# eurorack-passive-lpg.net
KiCad netlist of a schematic drawn in EAGLE
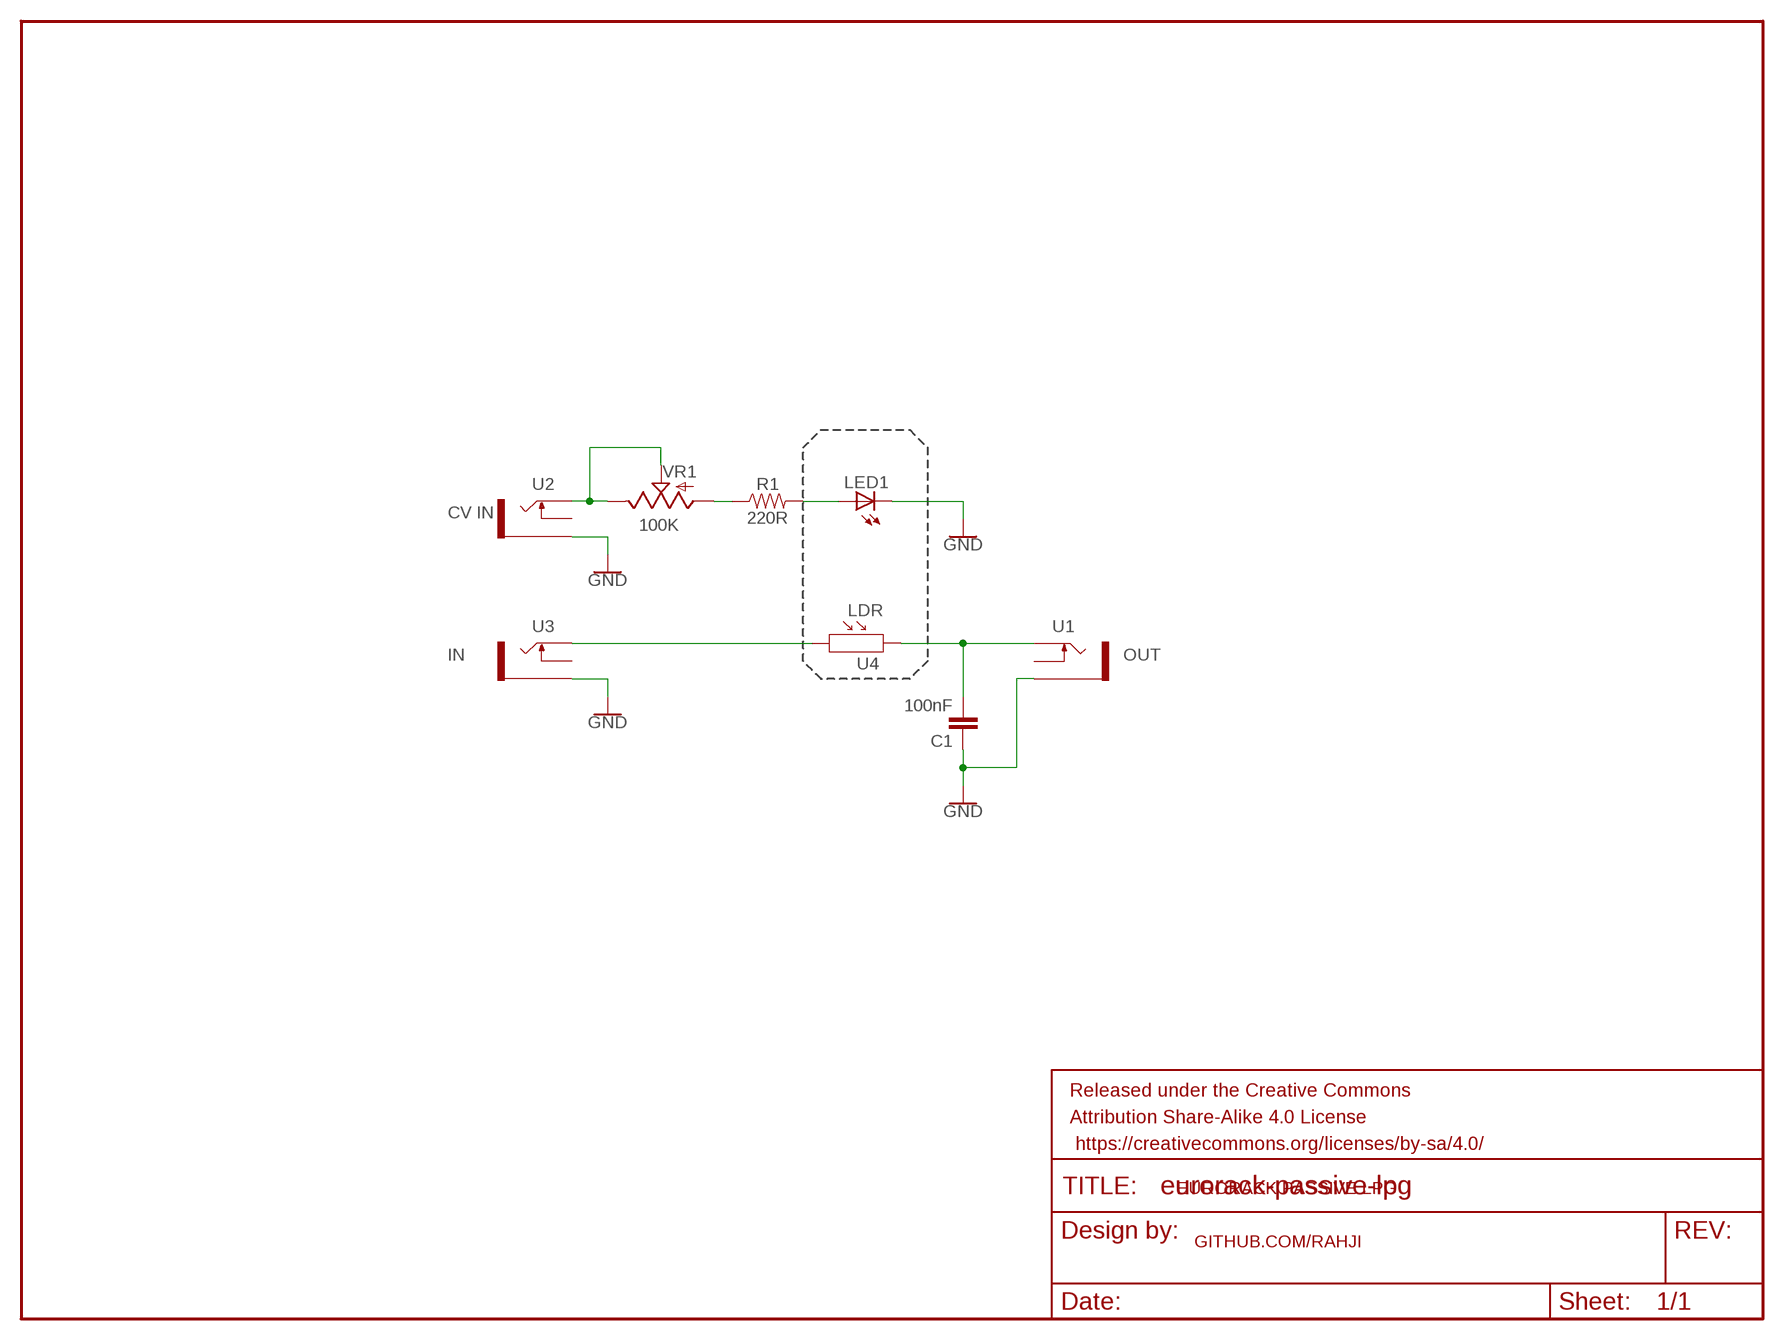
[diagram p0: schematic, sheet 1]

(export (version "E")
  (design (tool "Eeschema 10.0.6"))
  (components
    (comp (ref "C1")
      (value "100nF")
      (footprint "eagle-import:CAP-PTH-2.54")
      (libsource (lib "eagle-import") (part "22PF-PTH-2.54MM-200V-5%"))
    )
    (comp (ref "FRAME1")
      (value "FRAME-LETTERNO_PACKAGE")
      (footprint "eagle-import:DUMMY")
      (fields (field (name "DESIGNER") "Nobody"))
      (libsource (lib "eagle-import") (part "FRAME-LETTERNO_PACKAGE"))
    )
    (comp (ref "LED1")
      (value "LED5MM")
      (footprint "eagle-import:LED5MM")
      (libsource (lib "eagle-import") (part "LED5MM"))
    )
    (comp (ref "R1")
      (value "220R")
      (footprint "eagle-import:AXIAL-0.3")
      (libsource (lib "eagle-import") (part "100OHM-HORIZ-1/4W-1%"))
    )
    (comp (ref "U1")
      (value "OUT")
      (footprint "eagle-import:WQP-PJ301M-12_JACK")
      (libsource (lib "eagle-import") (part "THONKICONNNEW"))
    )
    (comp (ref "U2")
      (value "CV IN")
      (footprint "eagle-import:WQP-PJ301M-12_JACK")
      (libsource (lib "eagle-import") (part "THONKICONNNEW"))
    )
    (comp (ref "U3")
      (value "IN")
      (footprint "eagle-import:WQP-PJ301M-12_JACK")
      (libsource (lib "eagle-import") (part "THONKICONNNEW"))
    )
    (comp (ref "U4")
      (value "LDR")
      (footprint "eagle-import:SNR2-3.0")
      (fields (field (name "MPN") "PHOTORESISTOR-5528-10K"))
      (libsource (lib "eagle-import") (part "PHOTORESISTOR-5528-10K(2P-5.0X4.2MM)"))
    )
    (comp (ref "VR1")
      (value "100K")
      (footprint "eagle-import:9MM_SNAP-IN_POT")
      (libsource (lib "eagle-import") (part "9MM_SNAP-IN_POT_"))
    )
  )
  (nets
    (net (code "1") (name "GND") (class "Default")
      (node (ref "C1") (pin "1") (pinfunction "1_1") (pintype "passive"))
      (node (ref "LED1") (pin "K") (pinfunction "C_K") (pintype "passive"))
      (node (ref "U1") (pin "P$3_SLEEVE") (pinfunction "SLEEVE_P$3_SLEEVE") (pintype "passive"))
      (node (ref "U2") (pin "P$3_SLEEVE") (pinfunction "SLEEVE_P$3_SLEEVE") (pintype "passive"))
      (node (ref "U3") (pin "P$3_SLEEVE") (pinfunction "SLEEVE_P$3_SLEEVE") (pintype "passive"))
    )
    (net (code "2") (name "Net-(R1-1)") (class "Default")
      (node (ref "R1") (pin "P$1") (pinfunction "1_P$1") (pintype "passive"))
      (node (ref "VR1") (pin "1") (pinfunction "A_1") (pintype "passive"))
    )
    (net (code "3") (name "Net-(R1-2)") (class "Default")
      (node (ref "LED1") (pin "A") (pinfunction "A_A") (pintype "passive"))
      (node (ref "R1") (pin "P$2") (pinfunction "2_P$2") (pintype "passive"))
    )
    (net (code "4") (name "Net-(U1-TIP)") (class "Default")
      (node (ref "C1") (pin "2") (pinfunction "2_2") (pintype "passive"))
      (node (ref "U1") (pin "P$1_TIP") (pinfunction "TIP_P$1_TIP") (pintype "passive"))
      (node (ref "U4") (pin "2") (pinfunction "P$2_2") (pintype "bidirectional"))
    )
    (net (code "5") (name "Net-(U2-TIP)") (class "Default")
      (node (ref "U2") (pin "P$1_TIP") (pinfunction "TIP_P$1_TIP") (pintype "passive"))
      (node (ref "VR1") (pin "2") (pinfunction "S_2") (pintype "passive"))
      (node (ref "VR1") (pin "3") (pinfunction "E_3") (pintype "passive"))
    )
    (net (code "6") (name "Net-(U3-TIP)") (class "Default")
      (node (ref "U3") (pin "P$1_TIP") (pinfunction "TIP_P$1_TIP") (pintype "passive"))
      (node (ref "U4") (pin "1") (pinfunction "P$1_1") (pintype "bidirectional"))
    )
    (net (code "7") (name "unconnected-(U1-SWITCH-PadP$2_SWITCH)") (class "Default")
      (node (ref "U1") (pin "P$2_SWITCH") (pinfunction "SWITCH_P$2_SWITCH") (pintype "passive"))
    )
    (net (code "8") (name "unconnected-(U2-SWITCH-PadP$2_SWITCH)") (class "Default")
      (node (ref "U2") (pin "P$2_SWITCH") (pinfunction "SWITCH_P$2_SWITCH") (pintype "passive"))
    )
    (net (code "9") (name "unconnected-(U3-SWITCH-PadP$2_SWITCH)") (class "Default")
      (node (ref "U3") (pin "P$2_SWITCH") (pinfunction "SWITCH_P$2_SWITCH") (pintype "passive"))
    )
  )
)
